# MCU_Core.net
KiCad netlist of a schematic drawn in Altium Designer
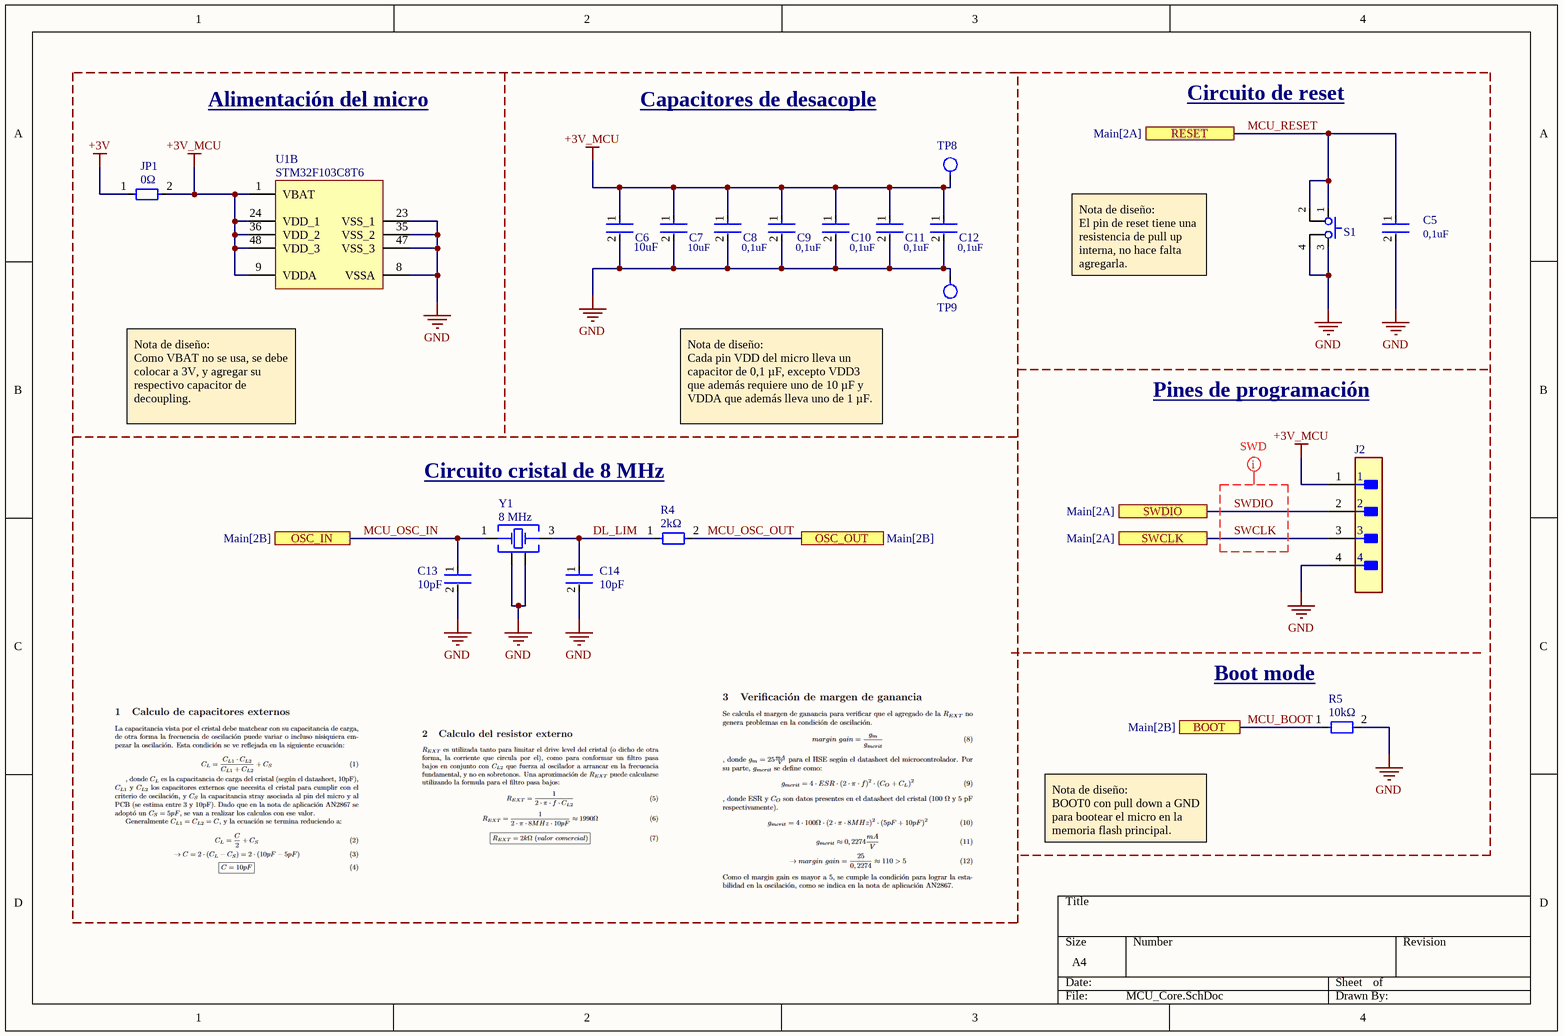
[diagram p0: MCU_Core.SchDoc]

(export (version "E")
  (design (tool "Eeschema 10.0.6"))
  (components
    (comp (ref "C5")
      (value "0.1uF")
      (footprint "CAP_0603")
      (description "Cap 0.1 uF 10V X7R 0603")
      (fields (field (name "CAPACITANCE") "0,1uF") (field (name "TOLERANCE") "10%"))
      (libsource (lib "Passive_Components") (part "Generic C"))
    )
    (comp (ref "C6")
      (value "10uF")
      (footprint "CAP_0603")
      (description "Cap 10 uF 10V X7R 0603")
      (fields (field (name "CAPACITANCE") "10uF") (field (name "TOLERANCE") "10%"))
      (libsource (lib "Passive_Components") (part "Generic C"))
    )
    (comp (ref "C7")
      (value "10uF")
      (footprint "CAP_0603")
      (description "Cap 10 uF 10V X7R 0603")
      (fields (field (name "CAPACITANCE") "10uF") (field (name "TOLERANCE") "10%"))
      (libsource (lib "Passive_Components") (part "Generic C"))
    )
    (comp (ref "C8")
      (value "0.1uF")
      (footprint "CAP_0603")
      (description "Cap 0.1 uF 10V X7R 0603")
      (fields (field (name "CAPACITANCE") "0,1uF") (field (name "TOLERANCE") "10%"))
      (libsource (lib "Passive_Components") (part "Generic C"))
    )
    (comp (ref "C9")
      (value "0.1uF")
      (footprint "CAP_0603")
      (description "Cap 0.1 uF 10V X7R 0603")
      (fields (field (name "CAPACITANCE") "0,1uF") (field (name "TOLERANCE") "10%"))
      (libsource (lib "Passive_Components") (part "Generic C"))
    )
    (comp (ref "C10")
      (value "0.1uF")
      (footprint "CAP_0603")
      (description "Cap 0.1 uF 10V X7R 0603")
      (fields (field (name "CAPACITANCE") "0,1uF") (field (name "TOLERANCE") "10%"))
      (libsource (lib "Passive_Components") (part "Generic C"))
    )
    (comp (ref "C11")
      (value "0.1uF")
      (footprint "CAP_0603")
      (description "Cap 0.1 uF 10V X7R 0603")
      (fields (field (name "CAPACITANCE") "0,1uF") (field (name "TOLERANCE") "10%"))
      (libsource (lib "Passive_Components") (part "Generic C"))
    )
    (comp (ref "C12")
      (value "0.1uF")
      (footprint "CAP_0603")
      (description "Cap 0.1 uF 10V X7R 0603")
      (fields (field (name "CAPACITANCE") "0,1uF") (field (name "TOLERANCE") "10%"))
      (libsource (lib "Passive_Components") (part "Generic C"))
    )
    (comp (ref "C13")
      (value "10pF")
      (footprint "CAP_0603")
      (description "Cap 10 pF 10V X7R 0603")
      (fields (field (name "CAPACITANCE") "10pF") (field (name "TOLERANCE") "10%"))
      (libsource (lib "Passive_Components") (part "Generic C"))
    )
    (comp (ref "C14")
      (value "10pF")
      (footprint "CAP_0603")
      (description "Cap 10 pF 10V X7R 0603")
      (fields (field (name "CAPACITANCE") "10pF") (field (name "TOLERANCE") "10%"))
      (libsource (lib "Passive_Components") (part "Generic C"))
    )
    (comp (ref "J2")
      (value "HTSW-104-07-G-S")
      (footprint "FP-HTSW-104-07-G-S-MFG")
      (description "CONN HEADER VERT 4POS 2.54MM")
      (libsource (lib "Connectors") (part "CMP-02766-001776-1"))
    )
    (comp (ref "JP1")
      (value "0Ω")
      (footprint "RES_0R_0603")
      (description "Generic Jumper")
      (fields (field (name "Comment") "Generic JP"))
      (libsource (lib "Passive_Components") (part "Generic JP"))
    )
    (comp (ref "R4")
      (value "2kΩ")
      (footprint "RES_0603")
      (description "RES  2k 1% 0603")
      (fields (field (name "Comment") "2k"))
      (libsource (lib "Passive_Components") (part "Generic R"))
    )
    (comp (ref "R5")
      (value "10kΩ")
      (footprint "RES_0603")
      (description "RES  10k 1% 0603")
      (fields (field (name "Comment") "10k"))
      (libsource (lib "Passive_Components") (part "Generic R"))
    )
    (comp (ref "S1")
      (value "Tactile push button 5,2mm x 5,2mm")
      (footprint "Switch Tactile 5,2mm x 5,2mm")
      (description "Switch Tactile SPST-NO 5,2mm x 5,2mm")
      (libsource (lib "Actuators") (part "Tactile push button 5,2mm x 5,2mm"))
    )
    (comp (ref "TP8")
      (value "Testpoint SMD")
      (footprint "Testpoint_SMD")
      (description "Testpoint SMD de 1mm de diametro.")
      (libsource (lib "Connectors") (part "Testpoint_SMD"))
    )
    (comp (ref "TP9")
      (value "Testpoint SMD")
      (footprint "Testpoint_SMD")
      (description "Testpoint SMD de 1mm de diametro.")
      (libsource (lib "Connectors") (part "Testpoint_SMD"))
    )
    (comp (ref "U1")
      (value "STM32F103C8T6")
      (footprint "STM-LQFP48_L")
      (libsource (lib "Microcontrollers") (part "STM32F103C8T6"))
    )
    (comp (ref "Y1")
      (value "Crystal SMD 4-P")
      (footprint "SMD5032-4P")
      (description "Cristal SMD 4-P 8 MHz")
      (fields
        (field (name "MANUFACTURER PART") "SX5B8.000F1020F30")
        (field (name "MANUFACTURER") "Shenzhen SCTF Elec")
        (field (name "FREQUENCY") "8 MHz")
      )
      (libsource (lib "Passive_Components") (part "Crystal SMD 4-P"))
    )
  )
  (nets
    (net (code "1") (name "+3V") (class "Default")
      (node (ref "JP1") (pin "1") (pinfunction "1_1") (pintype "passive"))
    )
    (net (code "2") (name "+3V_MCU") (class "Default")
      (node (ref "C10") (pin "1") (pinfunction "1_1") (pintype "passive"))
      (node (ref "C11") (pin "1") (pinfunction "1_1") (pintype "passive"))
      (node (ref "C12") (pin "1") (pinfunction "1_1") (pintype "passive"))
      (node (ref "C6") (pin "1") (pinfunction "1_1") (pintype "passive"))
      (node (ref "C7") (pin "1") (pinfunction "1_1") (pintype "passive"))
      (node (ref "C8") (pin "1") (pinfunction "1_1") (pintype "passive"))
      (node (ref "C9") (pin "1") (pinfunction "1_1") (pintype "passive"))
      (node (ref "J2") (pin "1") (pinfunction "1_1") (pintype "passive"))
      (node (ref "JP1") (pin "2") (pinfunction "2_2") (pintype "passive"))
      (node (ref "TP8") (pin "1") (pinfunction "1_1") (pintype "passive"))
      (node (ref "U1") (pin "1") (pinfunction "VBAT_1") (pintype "power_in"))
      (node (ref "U1") (pin "24") (pinfunction "VDD_1_24") (pintype "power_in"))
      (node (ref "U1") (pin "36") (pinfunction "VDD_2_36") (pintype "power_in"))
      (node (ref "U1") (pin "48") (pinfunction "VDD_3_48") (pintype "power_in"))
      (node (ref "U1") (pin "9") (pinfunction "VDDA_9") (pintype "power_in"))
    )
    (net (code "3") (name "/DL_LIM") (class "Default")
      (node (ref "C14") (pin "1") (pinfunction "1_1") (pintype "passive"))
      (node (ref "R4") (pin "1") (pinfunction "1_1") (pintype "passive"))
      (node (ref "Y1") (pin "3") (pinfunction "Crystal_3") (pintype "passive"))
    )
    (net (code "4") (name "/MCU_BOOT") (class "Default")
      (node (ref "R5") (pin "1") (pinfunction "1_1") (pintype "passive"))
    )
    (net (code "5") (name "/MCU_OSC_IN") (class "Default")
      (node (ref "C13") (pin "1") (pinfunction "1_1") (pintype "passive"))
      (node (ref "Y1") (pin "1") (pinfunction "Crystal_1") (pintype "passive"))
    )
    (net (code "6") (name "/MCU_OSC_OUT") (class "Default")
      (node (ref "R4") (pin "2") (pinfunction "2_2") (pintype "passive"))
    )
    (net (code "7") (name "/MCU_RESET") (class "Default")
      (node (ref "C5") (pin "1") (pinfunction "1_1") (pintype "passive"))
      (node (ref "S1") (pin "1") (pinfunction "1_1") (pintype "passive"))
      (node (ref "S1") (pin "2") (pinfunction "2_2") (pintype "passive"))
    )
    (net (code "8") (name "/SWCLK") (class "Default")
      (node (ref "J2") (pin "3") (pinfunction "3_3") (pintype "passive"))
    )
    (net (code "9") (name "/SWDIO") (class "Default")
      (node (ref "J2") (pin "2") (pinfunction "2_2") (pintype "passive"))
    )
    (net (code "10") (name "GND") (class "Default")
      (node (ref "C10") (pin "2") (pinfunction "2_2") (pintype "passive"))
      (node (ref "C11") (pin "2") (pinfunction "2_2") (pintype "passive"))
      (node (ref "C12") (pin "2") (pinfunction "2_2") (pintype "passive"))
      (node (ref "C13") (pin "2") (pinfunction "2_2") (pintype "passive"))
      (node (ref "C14") (pin "2") (pinfunction "2_2") (pintype "passive"))
      (node (ref "C5") (pin "2") (pinfunction "2_2") (pintype "passive"))
      (node (ref "C6") (pin "2") (pinfunction "2_2") (pintype "passive"))
      (node (ref "C7") (pin "2") (pinfunction "2_2") (pintype "passive"))
      (node (ref "C8") (pin "2") (pinfunction "2_2") (pintype "passive"))
      (node (ref "C9") (pin "2") (pinfunction "2_2") (pintype "passive"))
      (node (ref "J2") (pin "4") (pinfunction "4_4") (pintype "passive"))
      (node (ref "R5") (pin "2") (pinfunction "2_2") (pintype "passive"))
      (node (ref "S1") (pin "3") (pinfunction "3_3") (pintype "passive"))
      (node (ref "S1") (pin "4") (pinfunction "4_4") (pintype "passive"))
      (node (ref "TP9") (pin "1") (pinfunction "1_1") (pintype "passive"))
      (node (ref "U1") (pin "23") (pinfunction "VSS_1_23") (pintype "power_in"))
      (node (ref "U1") (pin "35") (pinfunction "VSS_2_35") (pintype "power_in"))
      (node (ref "U1") (pin "47") (pinfunction "VSS_3_47") (pintype "power_in"))
      (node (ref "U1") (pin "8") (pinfunction "VSSA_8") (pintype "power_in"))
      (node (ref "Y1") (pin "2") (pinfunction "GND_&_Lid_2") (pintype "passive"))
      (node (ref "Y1") (pin "4") (pinfunction "GND_&_Lid_4") (pintype "passive"))
    )
  )
)
